# Connector.net
KiCad netlist of a schematic drawn in Altium Designer
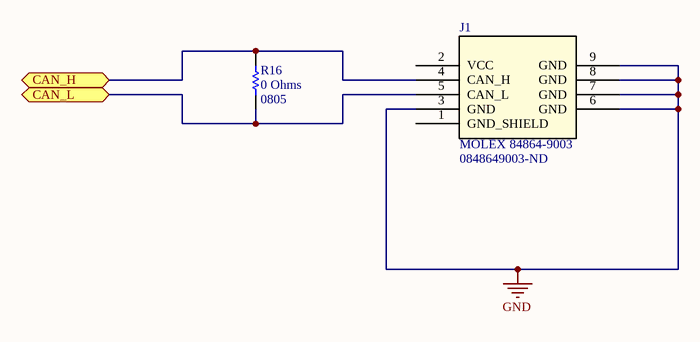
[diagram p0: Connector.SchDoc]

(export (version "E")
  (design (tool "Eeschema 10.0.6"))
  (components
    (comp (ref "J1")
      (value "MOLEX 84864-9003")
      (footprint "MOLEX 84864-9003")
      (description "CAN Micro-Change M12, Right Angle, Male")
      (fields (field (name "SUPPLIER PART NUMBER 1") "0848649003-ND"))
      (libsource (lib "Connectors and Headers") (part "MOLEX 84864-9003"))
    )
    (comp (ref "R16")
      (value "DNP")
      (footprint "RES0805")
      (description "RES SMD 0.0 OHM JUMPER 1/8W 0805")
      (fields
        (field (name "TOLERANCE") "Jumper")
        (field (name "RESISTANCE") "0 Ohms")
        (field (name "PACKAGE / CASE") "0805")
      )
      (libsource (lib "Resistors") (part "DNP"))
    )
  )
  (nets
    (net (code "1") (name "/CAN_H") (class "Default")
      (node (ref "J1") (pin "4") (pinfunction "CAN_H_4") (pintype "passive"))
      (node (ref "R16") (pin "2") (pinfunction "2_2") (pintype "passive"))
    )
    (net (code "2") (name "/CAN_L") (class "Default")
      (node (ref "J1") (pin "5") (pinfunction "CAN_L_5") (pintype "passive"))
      (node (ref "R16") (pin "1") (pinfunction "1_1") (pintype "passive"))
    )
    (net (code "3") (name "GND") (class "Default")
      (node (ref "J1") (pin "3") (pinfunction "GND_3") (pintype "passive"))
      (node (ref "J1") (pin "6") (pinfunction "GND_6") (pintype "passive"))
      (node (ref "J1") (pin "7") (pinfunction "GND_7") (pintype "passive"))
      (node (ref "J1") (pin "8") (pinfunction "GND_8") (pintype "passive"))
      (node (ref "J1") (pin "9") (pinfunction "GND_9") (pintype "passive"))
    )
    (net (code "4") (name "unconnected-(J1-GND_SHIELD-Pad1)") (class "Default")
      (node (ref "J1") (pin "1") (pinfunction "GND_SHIELD_1") (pintype "passive"))
    )
    (net (code "5") (name "unconnected-(J1-VCC-Pad2)") (class "Default")
      (node (ref "J1") (pin "2") (pinfunction "VCC_2") (pintype "passive"))
    )
  )
)
